# feedback_device_REV2.net
KiCad netlist of a schematic drawn in EAGLE
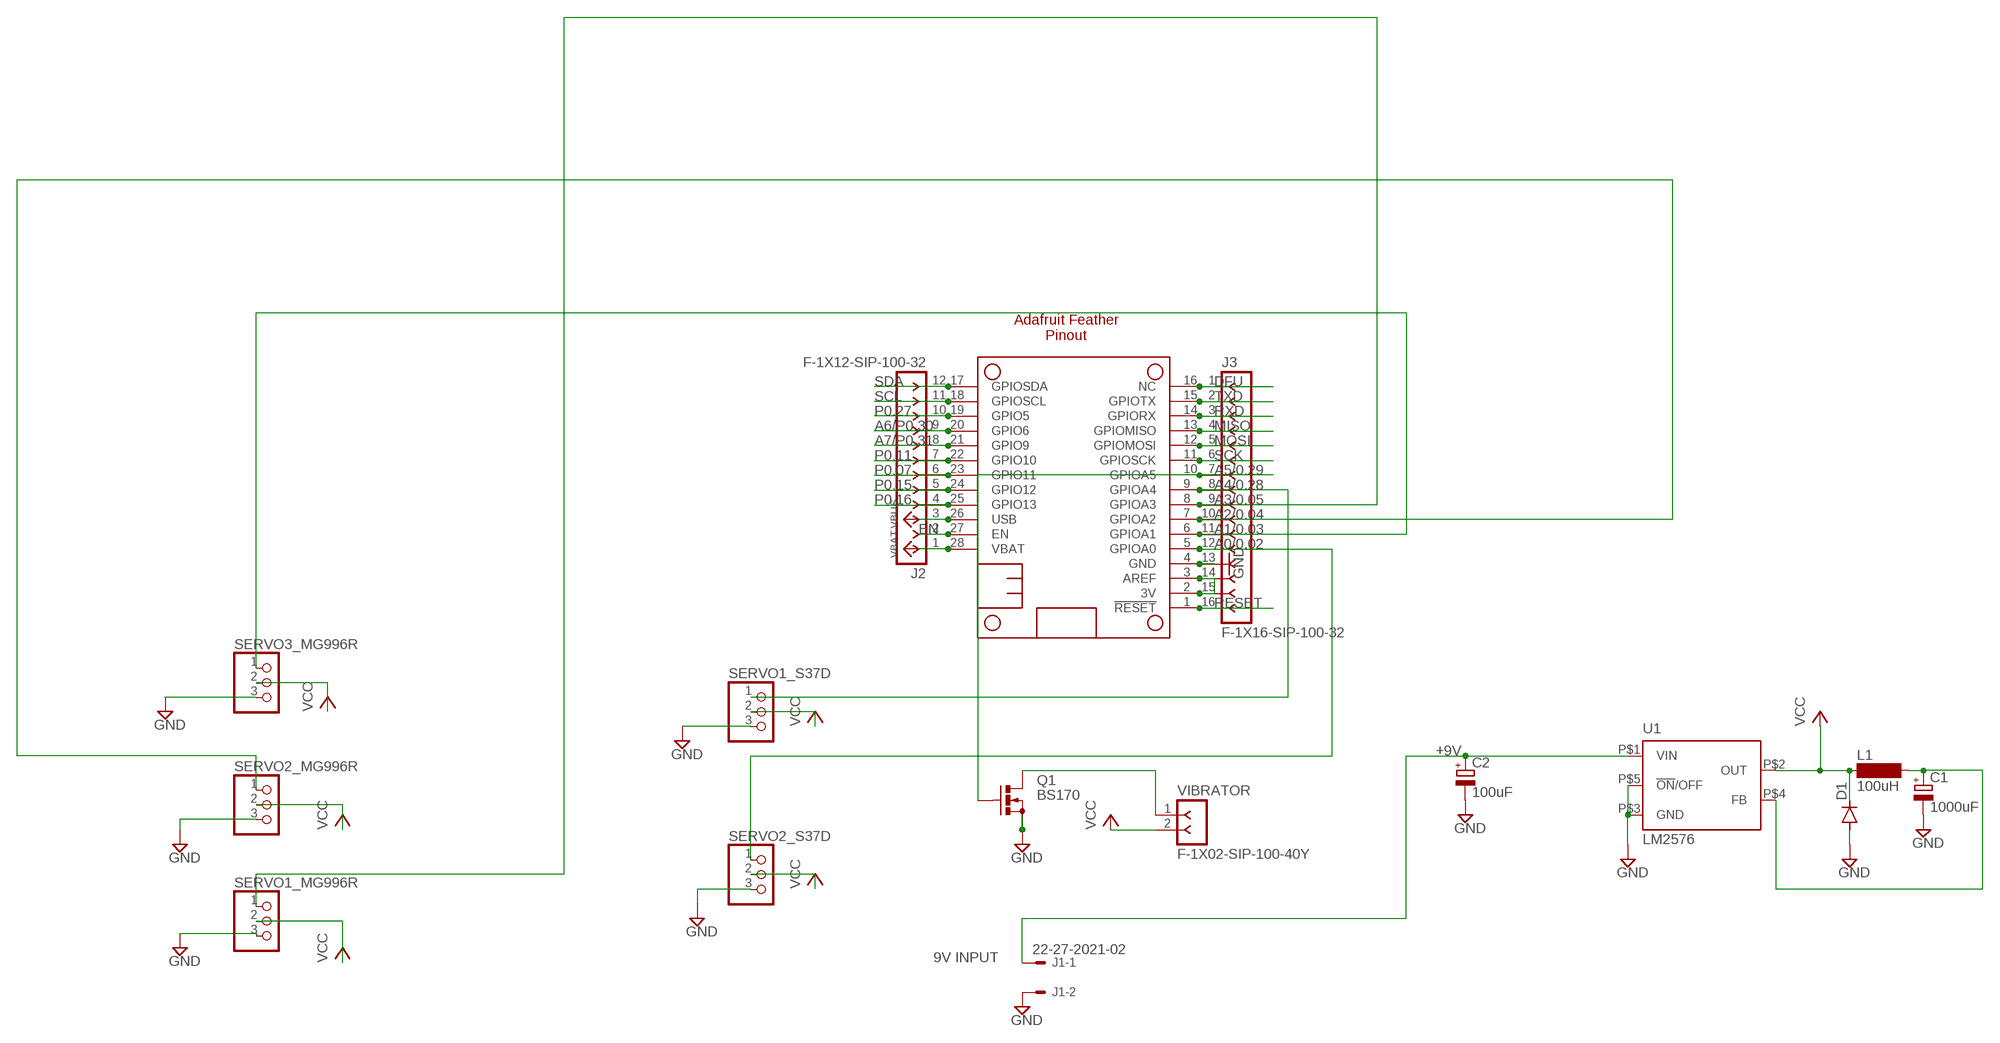
[diagram p0: schematic, sheet 1]

(export (version "E")
  (design (tool "Eeschema 10.0.6"))
  (components
    (comp (ref "C1")
      (value "1000uF")
      (footprint "eagle-import:E5-8,5")
      (libsource (lib "eagle-import") (part "CPOL-EUE5-8.5"))
    )
    (comp (ref "C2")
      (value "100uF")
      (footprint "eagle-import:E2,5-7")
      (libsource (lib "eagle-import") (part "CPOL-EUE2.5-7"))
    )
    (comp (ref "D1")
      (value "DIODE-SMB")
      (footprint "eagle-import:SMB")
      (libsource (lib "eagle-import") (part "DIODE-SMB"))
    )
    (comp (ref "J1")
      (value "22-27-2021-02")
      (footprint "eagle-import:6410-02")
      (fields (field (name "MF") "MOLEX"))
      (libsource (lib "eagle-import") (part "22-?-0227-2021"))
    )
    (comp (ref "J2")
      (value "F-1X12-SIP-100-32")
      (footprint "eagle-import:SIP-100-12-32")
      (libsource (lib "eagle-import") (part "F-1X12-SIP-100-32"))
    )
    (comp (ref "J3")
      (value "F-1X16-SIP-100-32")
      (footprint "eagle-import:SIP-100-16-32")
      (libsource (lib "eagle-import") (part "F-1X16-SIP-100-32"))
    )
    (comp (ref "L1")
      (value "100uH")
      (footprint "eagle-import:SD75")
      (libsource (lib "eagle-import") (part "SD75"))
    )
    (comp (ref "MS1")
      (value "FEATHERWING_NODIM")
      (footprint "eagle-import:FEATHERWING_NODIM")
      (libsource (lib "eagle-import") (part "FEATHERWING_NODIM"))
    )
    (comp (ref "Q1")
      (value "BS170")
      (footprint "eagle-import:SOT54E")
      (libsource (lib "eagle-import") (part "BS170"))
    )
    (comp (ref "SERVO1_MG996R")
      (value "PINHD-1X3")
      (footprint "eagle-import:1X03")
      (libsource (lib "eagle-import") (part "PINHD-1X3"))
    )
    (comp (ref "SERVO1_S37D")
      (value "PINHD-1X3")
      (footprint "eagle-import:1X03")
      (libsource (lib "eagle-import") (part "PINHD-1X3"))
    )
    (comp (ref "SERVO2_MG996R")
      (value "PINHD-1X3")
      (footprint "eagle-import:1X03")
      (libsource (lib "eagle-import") (part "PINHD-1X3"))
    )
    (comp (ref "SERVO2_S37D")
      (value "PINHD-1X3")
      (footprint "eagle-import:1X03")
      (libsource (lib "eagle-import") (part "PINHD-1X3"))
    )
    (comp (ref "SERVO3_MG996R")
      (value "PINHD-1X3")
      (footprint "eagle-import:1X03")
      (libsource (lib "eagle-import") (part "PINHD-1X3"))
    )
    (comp (ref "U1")
      (value "LM2576")
      (footprint "eagle-import:LM2576")
      (libsource (lib "eagle-import") (part "LM2576"))
    )
    (comp (ref "VIBRATOR")
      (value "F-1X02-SIP-100-40Y")
      (footprint "eagle-import:SIP-100-02-40Y")
      (libsource (lib "eagle-import") (part "F-1X02-SIP-100-40Y"))
    )
  )
  (nets
    (net (code "1") (name "/A0{slash}0.02") (class "Default")
      (node (ref "J3") (pin "12") (pinfunction "12_12") (pintype "passive"))
      (node (ref "MS1") (pin "5") (pinfunction "GPIOA0_5") (pintype "bidirectional"))
      (node (ref "SERVO2_S37D") (pin "1") (pinfunction "1_1") (pintype "passive"))
    )
    (net (code "2") (name "/A1{slash}0.03") (class "Default")
      (node (ref "J3") (pin "11") (pinfunction "11_11") (pintype "passive"))
      (node (ref "MS1") (pin "6") (pinfunction "GPIOA1_6") (pintype "bidirectional"))
      (node (ref "SERVO3_MG996R") (pin "1") (pinfunction "1_1") (pintype "passive"))
    )
    (net (code "3") (name "/A2{slash}0.04") (class "Default")
      (node (ref "J3") (pin "10") (pinfunction "10_10") (pintype "passive"))
      (node (ref "MS1") (pin "7") (pinfunction "GPIOA2_7") (pintype "bidirectional"))
      (node (ref "SERVO2_MG996R") (pin "1") (pinfunction "1_1") (pintype "passive"))
    )
    (net (code "4") (name "/A3{slash}0.05") (class "Default")
      (node (ref "J3") (pin "9") (pinfunction "9_9") (pintype "passive"))
      (node (ref "MS1") (pin "8") (pinfunction "GPIOA3_8") (pintype "bidirectional"))
      (node (ref "SERVO1_MG996R") (pin "1") (pinfunction "1_1") (pintype "passive"))
    )
    (net (code "5") (name "/A4{slash}0.28") (class "Default")
      (node (ref "J3") (pin "8") (pinfunction "8_8") (pintype "passive"))
      (node (ref "MS1") (pin "9") (pinfunction "GPIOA4_9") (pintype "bidirectional"))
      (node (ref "SERVO1_S37D") (pin "1") (pinfunction "1_1") (pintype "passive"))
    )
    (net (code "6") (name "/A5{slash}0.29") (class "Default")
      (node (ref "J3") (pin "7") (pinfunction "7_7") (pintype "passive"))
      (node (ref "MS1") (pin "10") (pinfunction "GPIOA5_10") (pintype "bidirectional"))
      (node (ref "Q1") (pin "G") (pinfunction "G_G") (pintype "passive"))
    )
    (net (code "7") (name "/A6{slash}P0.30") (class "Default")
      (node (ref "J2") (pin "9") (pinfunction "9_9") (pintype "passive"))
      (node (ref "MS1") (pin "20") (pinfunction "GPIO6_20") (pintype "bidirectional"))
    )
    (net (code "8") (name "/A7{slash}P0.31") (class "Default")
      (node (ref "J2") (pin "8") (pinfunction "8_8") (pintype "passive"))
      (node (ref "MS1") (pin "21") (pinfunction "GPIO9_21") (pintype "bidirectional"))
    )
    (net (code "9") (name "/DFU") (class "Default")
      (node (ref "J3") (pin "1") (pinfunction "1_1") (pintype "passive"))
      (node (ref "MS1") (pin "16") (pinfunction "NC_16") (pintype "passive"))
    )
    (net (code "10") (name "/EN") (class "Default")
      (node (ref "J2") (pin "2") (pinfunction "2_2") (pintype "passive"))
      (node (ref "MS1") (pin "27") (pinfunction "EN_27") (pintype "passive"))
    )
    (net (code "11") (name "/MISO") (class "Default")
      (node (ref "J3") (pin "4") (pinfunction "4_4") (pintype "passive"))
      (node (ref "MS1") (pin "13") (pinfunction "GPIOMISO_13") (pintype "bidirectional"))
    )
    (net (code "12") (name "/MOSI") (class "Default")
      (node (ref "J3") (pin "5") (pinfunction "5_5") (pintype "passive"))
      (node (ref "MS1") (pin "12") (pinfunction "GPIOMOSI_12") (pintype "bidirectional"))
    )
    (net (code "13") (name "/P0.07") (class "Default")
      (node (ref "J2") (pin "6") (pinfunction "6_6") (pintype "passive"))
      (node (ref "MS1") (pin "23") (pinfunction "GPIO11_23") (pintype "bidirectional"))
    )
    (net (code "14") (name "/P0.11") (class "Default")
      (node (ref "J2") (pin "7") (pinfunction "7_7") (pintype "passive"))
      (node (ref "MS1") (pin "22") (pinfunction "GPIO10_22") (pintype "bidirectional"))
    )
    (net (code "15") (name "/P0.15") (class "Default")
      (node (ref "J2") (pin "5") (pinfunction "5_5") (pintype "passive"))
      (node (ref "MS1") (pin "24") (pinfunction "GPIO12_24") (pintype "bidirectional"))
    )
    (net (code "16") (name "/P0.16") (class "Default")
      (node (ref "J2") (pin "4") (pinfunction "4_4") (pintype "passive"))
      (node (ref "MS1") (pin "25") (pinfunction "GPIO13_25") (pintype "bidirectional"))
    )
    (net (code "17") (name "/P0.27") (class "Default")
      (node (ref "J2") (pin "10") (pinfunction "10_10") (pintype "passive"))
      (node (ref "MS1") (pin "19") (pinfunction "GPIO5_19") (pintype "bidirectional"))
    )
    (net (code "18") (name "/RESET") (class "Default")
      (node (ref "J3") (pin "16") (pinfunction "16_16") (pintype "passive"))
      (node (ref "MS1") (pin "1") (pinfunction "~{RESET}_1") (pintype "input"))
    )
    (net (code "19") (name "/RXD") (class "Default")
      (node (ref "J3") (pin "3") (pinfunction "3_3") (pintype "passive"))
      (node (ref "MS1") (pin "14") (pinfunction "GPIORX_14") (pintype "bidirectional"))
    )
    (net (code "20") (name "/SCK") (class "Default")
      (node (ref "J3") (pin "6") (pinfunction "6_6") (pintype "passive"))
      (node (ref "MS1") (pin "11") (pinfunction "GPIOSCK_11") (pintype "bidirectional"))
    )
    (net (code "21") (name "/SCL") (class "Default")
      (node (ref "J2") (pin "11") (pinfunction "11_11") (pintype "passive"))
      (node (ref "MS1") (pin "18") (pinfunction "GPIOSCL_18") (pintype "bidirectional"))
    )
    (net (code "22") (name "/SDA") (class "Default")
      (node (ref "J2") (pin "12") (pinfunction "12_12") (pintype "passive"))
      (node (ref "MS1") (pin "17") (pinfunction "GPIOSDA_17") (pintype "bidirectional"))
    )
    (net (code "23") (name "/TXD") (class "Default")
      (node (ref "J3") (pin "2") (pinfunction "2_2") (pintype "passive"))
      (node (ref "MS1") (pin "15") (pinfunction "GPIOTX_15") (pintype "bidirectional"))
    )
    (net (code "24") (name "GND") (class "Default")
      (node (ref "C1") (pin "-") (pinfunction "-_-") (pintype "passive"))
      (node (ref "C2") (pin "-") (pinfunction "-_-") (pintype "passive"))
      (node (ref "D1") (pin "A") (pinfunction "A_A") (pintype "passive"))
      (node (ref "J1") (pin "2") (pinfunction "S_2") (pintype "passive"))
      (node (ref "J3") (pin "13") (pinfunction "13_13") (pintype "passive"))
      (node (ref "MS1") (pin "4") (pinfunction "GND_4") (pintype "power_in"))
      (node (ref "Q1") (pin "S") (pinfunction "S_S") (pintype "passive"))
      (node (ref "SERVO1_MG996R") (pin "3") (pinfunction "3_3") (pintype "passive"))
      (node (ref "SERVO1_S37D") (pin "3") (pinfunction "3_3") (pintype "passive"))
      (node (ref "SERVO2_MG996R") (pin "3") (pinfunction "3_3") (pintype "passive"))
      (node (ref "SERVO2_S37D") (pin "3") (pinfunction "3_3") (pintype "passive"))
      (node (ref "SERVO3_MG996R") (pin "3") (pinfunction "3_3") (pintype "passive"))
      (node (ref "U1") (pin "P$3") (pinfunction "GND_P$3") (pintype "power_in"))
      (node (ref "U1") (pin "P$5") (pinfunction "~{ON}/OFF_P$5") (pintype "input"))
    )
    (net (code "25") (name "Net-(J1A-S)") (class "Default")
      (node (ref "C2") (pin "+") (pinfunction "+_+") (pintype "passive"))
      (node (ref "J1") (pin "1") (pinfunction "S_1") (pintype "passive"))
      (node (ref "U1") (pin "P$1") (pinfunction "VIN_P$1") (pintype "input"))
    )
    (net (code "26") (name "Net-(MS1-3V)") (class "Default")
      (node (ref "J3") (pin "14") (pinfunction "14_14") (pintype "passive"))
      (node (ref "J3") (pin "15") (pinfunction "15_15") (pintype "passive"))
      (node (ref "MS1") (pin "2") (pinfunction "3V_2") (pintype "power_in"))
      (node (ref "MS1") (pin "3") (pinfunction "AREF_3") (pintype "passive"))
    )
    (net (code "27") (name "Net-(Q1-PadD)") (class "Default")
      (node (ref "Q1") (pin "D") (pinfunction "D_D") (pintype "passive"))
      (node (ref "VIBRATOR") (pin "1") (pinfunction "1_1") (pintype "passive"))
    )
    (net (code "28") (name "Net-(U1-FB)") (class "Default")
      (node (ref "C1") (pin "+") (pinfunction "+_+") (pintype "passive"))
      (node (ref "L1") (pin "2") (pinfunction "2_2") (pintype "passive"))
      (node (ref "U1") (pin "P$4") (pinfunction "FB_P$4") (pintype "input"))
    )
    (net (code "29") (name "VBAT") (class "Default")
      (node (ref "J2") (pin "1") (pinfunction "1_1") (pintype "passive"))
      (node (ref "MS1") (pin "28") (pinfunction "VBAT_28") (pintype "power_in"))
    )
    (net (code "30") (name "VBUS") (class "Default")
      (node (ref "J2") (pin "3") (pinfunction "3_3") (pintype "passive"))
      (node (ref "MS1") (pin "26") (pinfunction "USB_26") (pintype "power_in"))
    )
    (net (code "31") (name "VCC") (class "Default")
      (node (ref "D1") (pin "C") (pinfunction "C_C") (pintype "passive"))
      (node (ref "L1") (pin "1") (pinfunction "1_1") (pintype "passive"))
      (node (ref "SERVO1_MG996R") (pin "2") (pinfunction "2_2") (pintype "passive"))
      (node (ref "SERVO1_S37D") (pin "2") (pinfunction "2_2") (pintype "passive"))
      (node (ref "SERVO2_MG996R") (pin "2") (pinfunction "2_2") (pintype "passive"))
      (node (ref "SERVO2_S37D") (pin "2") (pinfunction "2_2") (pintype "passive"))
      (node (ref "SERVO3_MG996R") (pin "2") (pinfunction "2_2") (pintype "passive"))
      (node (ref "U1") (pin "P$2") (pinfunction "OUT_P$2") (pintype "output"))
      (node (ref "VIBRATOR") (pin "2") (pinfunction "2_2") (pintype "passive"))
    )
  )
)
